# Current_Draw_Circuit.net
KiCad netlist of a schematic drawn in Altium Designer
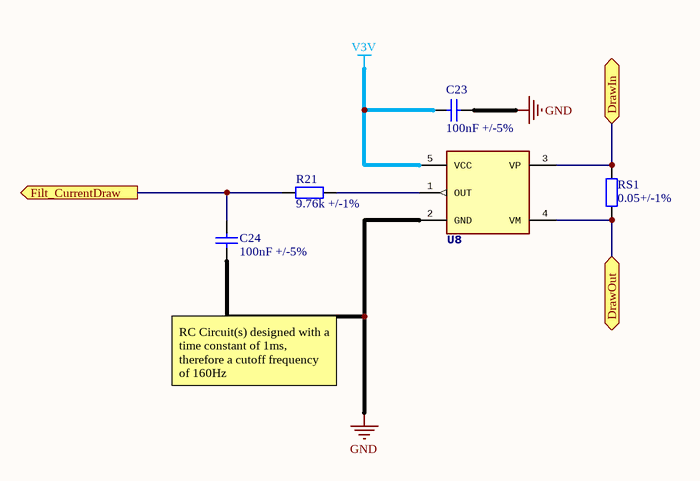
[diagram p0: Current_Draw_Circuit.SchDoc]

(export (version "E")
  (design (tool "Eeschema 10.0.6"))
  (components
    (comp (ref "C23")
      (value "100nF +/-5%")
      (footprint "CAPC1608X06N (0603)")
      (description "Capacitor (Semiconductor SIM Model)")
      (fields (field (name "Comment") "Cap Semi") (field (name "PUBLISHER") "Altium Limited"))
      (libsource (lib "miStepper_SchematicLib") (part "Cap Semi"))
    )
    (comp (ref "C24")
      (value "100nF +/-5%")
      (footprint "CAPC1608X06N (0603)")
      (description "Capacitor (Semiconductor SIM Model)")
      (fields (field (name "Comment") "Cap Semi") (field (name "PUBLISHER") "Altium Limited"))
      (libsource (lib "miStepper_SchematicLib") (part "Cap Semi"))
    )
    (comp (ref "R21")
      (value "9.76k +/-1%")
      (footprint "RESC1608X06N (0603)")
      (description "Resistor")
      (fields (field (name "Comment") "Res") (field (name "PUBLISHER") "Altium Limited"))
      (libsource (lib "") (part "Res_1"))
    )
    (comp (ref "RS1")
      (value "0.05+/-1%")
      (footprint "RESC2012X06N (0805)")
      (description "Resistor")
      (fields (field (name "Comment") "Res") (field (name "PUBLISHER") "Altium Limited"))
      (libsource (lib "miStepper_SchematicLib") (part "Res"))
    )
    (comp (ref "U8")
      (value "CS30xL")
      (footprint "SOT95P280X145-5N")
      (description "High side current sense high voltage op amp")
      (fields (field (name "MOUSER_PART_NUMBER") "511-CS30xL") (field (name "RS_PART_NUMBER") "8607514"))
      (libsource (lib "miStepper_SchematicLib") (part "CS30xL"))
    )
  )
  (nets
    (net (code "1") (name "/DrawIn") (class "Default")
      (node (ref "RS1") (pin "2") (pinfunction "2_2") (pintype "passive"))
      (node (ref "U8") (pin "3") (pinfunction "VP_3") (pintype "power_in"))
    )
    (net (code "2") (name "/DrawOut") (class "Default")
      (node (ref "RS1") (pin "1") (pinfunction "1_1") (pintype "passive"))
      (node (ref "U8") (pin "4") (pinfunction "VM_4") (pintype "power_in"))
    )
    (net (code "3") (name "/Filt_CurrentDraw") (class "Default")
      (node (ref "C24") (pin "2") (pinfunction "2_2") (pintype "passive"))
      (node (ref "R21") (pin "1") (pinfunction "1_1") (pintype "passive"))
    )
    (net (code "4") (name "GND") (class "Default")
      (node (ref "C23") (pin "1") (pinfunction "1_1") (pintype "passive"))
      (node (ref "C24") (pin "1") (pinfunction "1_1") (pintype "passive"))
      (node (ref "U8") (pin "2") (pinfunction "GND_2") (pintype "power_in"))
    )
    (net (code "5") (name "Net-(U8-OUT)") (class "Default")
      (node (ref "R21") (pin "2") (pinfunction "2_2") (pintype "passive"))
      (node (ref "U8") (pin "1") (pinfunction "OUT_1") (pintype "output"))
    )
    (net (code "6") (name "V3V") (class "Default")
      (node (ref "C23") (pin "2") (pinfunction "2_2") (pintype "passive"))
      (node (ref "U8") (pin "5") (pinfunction "VCC_5") (pintype "power_in"))
    )
  )
)
